# X99_20241008.net
KiCad netlist of a schematic drawn in Altium Designer
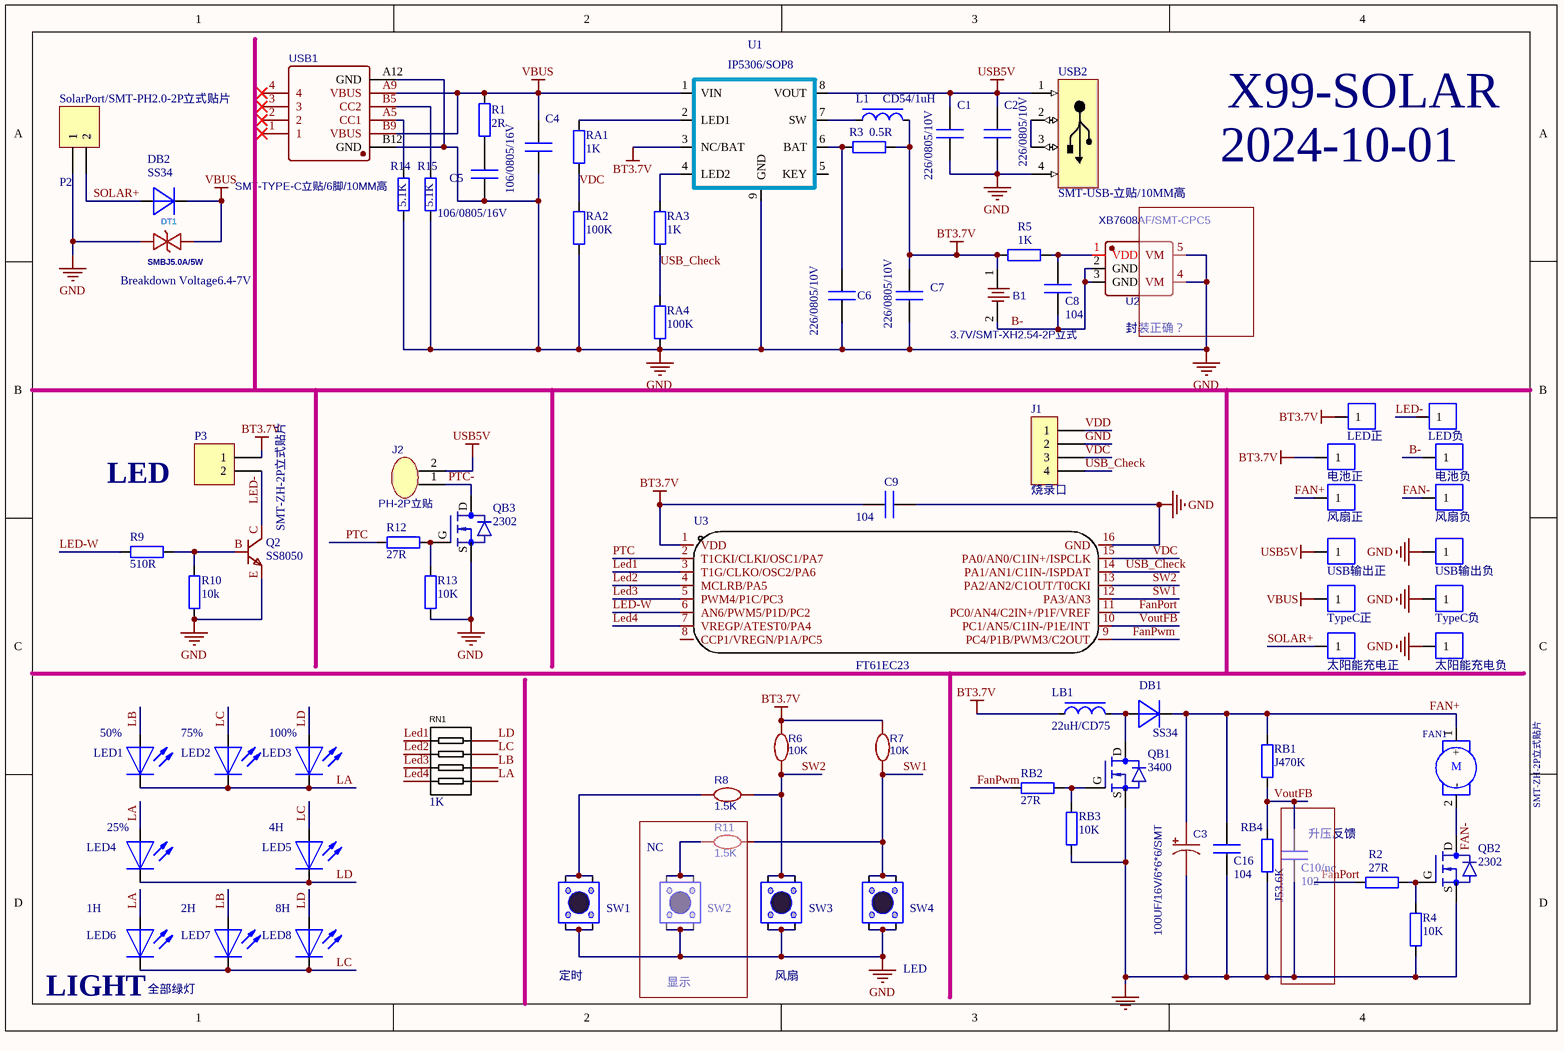
[diagram p0: X99_20241008.SchDoc]

(export (version "E")
  (design (tool "Eeschema 10.0.6"))
  (components
    (comp (ref "B1")
      (value "3.7V/SMT-XH2.54-2P立式")
      (footprint "SMT-XH2.54-2P立式")
      (fields (field (name "BOM_MANUFACTURER PART") "CR1220-2") (field (name "BOM_SUPPLIER PART") "C70381"))
      (libsource (lib "altium-import") (part "root_3_12V_"))
    )
    (comp (ref "C1")
      (value "226/0805/10V")
      (footprint "SMT-0805C")
      (libsource (lib "KENNED 原理图标准封装-20160624") (part "Cap"))
    )
    (comp (ref "C2")
      (value "226/0805/10V")
      (footprint "SMT-0805C")
      (libsource (lib "KENNED 原理图标准封装-20160624") (part "Cap"))
    )
    (comp (ref "C3")
      (value "100UF/16V/6*6*6/SMT")
      (footprint "CS 6*6 - V")
      (fields
        (field (name "BOM_SUPPLIER PART") "C365767")
        (field (name "BOM_MANUFACTURER PART") "RC050M4R7LO5*11TH-2A1E")
        (field (name "CONTRIBUTOR") "s-dawn")
      )
      (libsource (lib "altium-import") (part "root_0_220uF/35V_"))
    )
    (comp (ref "C4")
      (value "106/0805/16V")
      (footprint "SMT-0805C")
      (libsource (lib "KENNED 原理图标准封装-20160624") (part "Cap"))
    )
    (comp (ref "C5")
      (value "106/0805/16V")
      (footprint "SMT-0805C")
      (libsource (lib "KENNED 原理图标准封装-20160624") (part "Cap"))
    )
    (comp (ref "C6")
      (value "226/0805/10V")
      (footprint "SMT-0805C")
      (libsource (lib "KENNED 原理图标准封装-20160624") (part "Cap"))
    )
    (comp (ref "C7")
      (value "226/0805/10V")
      (footprint "SMT-0805C")
      (libsource (lib "KENNED 原理图标准封装-20160624") (part "Cap"))
    )
    (comp (ref "C8")
      (value "104")
      (footprint "SMT-0603C")
      (libsource (lib "KENNED 原理图标准封装-20160624") (part "Cap"))
    )
    (comp (ref "C9")
      (value "104")
      (footprint "SMT-0603C")
      (libsource (lib "KENNED 原理图标准封装-20180426") (part "Cap"))
    )
    (comp (ref "C10/nc")
      (value "102")
      (footprint "SMT-0603C")
      (libsource (lib "KENNED 原理图标准封装-20160624") (part "Cap"))
    )
    (comp (ref "C16")
      (value "104")
      (footprint "SMT-0603C")
      (libsource (lib "KENNED 原理图标准封装-20160624") (part "Cap"))
    )
    (comp (ref "DB1")
      (value "SS34")
      (footprint "SMT-SMA(DO-214AC)")
      (libsource (lib "KENNED 原理图标准封装-20180426") (part "Diode"))
    )
    (comp (ref "DB2")
      (value "SS34")
      (footprint "SMT-SMA(DO-214AC)")
      (libsource (lib "KENNED 原理图标准封装-20180426") (part "Diode"))
    )
    (comp (ref "DT1")
      (value "SMBJ5.0A/5W")
      (footprint "SMT-SMB(DO-214AA)")
      (fields (field (name "MANUFACTURER") "宏迦橙") (field (name "MANUFACTURER PART") "SMBJ5.0CA"))
      (libsource (lib "altium-import") (part "root_0_SMBJ5.0CA_C19077559_"))
    )
    (comp (ref "FAN1")
      (value "SMT-ZH-2P立式贴片")
      (footprint "SMT-ZH-2AB")
      (libsource (lib "*") (part "MotorDC-P"))
    )
    (comp (ref "J1") (value "烧录口") (footprint "SMT-烧录口") (libsource (lib "排针") (part "Pin HDR1X4")))
    (comp (ref "J2")
      (value "PH-2P立贴")
      (footprint "SMT-PH2.0-2P立式贴片")
      (fields (field (name "CONTRIBUTOR") "guilingSong"))
      (libsource (lib "altium-import") (part "root_0_mirrored_2P_"))
    )
    (comp (ref "L1")
      (value "CD54/1uH")
      (footprint "CD54")
      (libsource (lib "KENNED 原理图标准封装-20180426") (part "L Core"))
    )
    (comp (ref "LB1")
      (value "22uH/CD75")
      (footprint "SMT-CD75_L")
      (libsource (lib "KENNED 原理图标准封装-20180426") (part "L Core"))
    )
    (comp (ref "LED1")
      (value "~")
      (footprint "SMT-0603LED（绿灯）")
      (libsource (lib "KENNED 原理图标准封装-20160624") (part "LED"))
    )
    (comp (ref "LED2")
      (value "~")
      (footprint "SMT-0603LED（绿灯）")
      (libsource (lib "KENNED 原理图标准封装-20160624") (part "LED"))
    )
    (comp (ref "LED3")
      (value "~")
      (footprint "SMT-0603LED（绿灯）")
      (libsource (lib "KENNED 原理图标准封装-20160624") (part "LED"))
    )
    (comp (ref "LED4")
      (value "~")
      (footprint "SMT-0603LED（绿灯）")
      (libsource (lib "KENNED 原理图标准封装-20160624") (part "LED"))
    )
    (comp (ref "LED5")
      (value "~")
      (footprint "SMT-0603LED（绿灯）")
      (libsource (lib "KENNED 原理图标准封装-20160624") (part "LED"))
    )
    (comp (ref "LED6")
      (value "~")
      (footprint "SMT-0603LED（绿灯）")
      (libsource (lib "KENNED 原理图标准封装-20160624") (part "LED"))
    )
    (comp (ref "LED7")
      (value "~")
      (footprint "SMT-0603LED（绿灯）")
      (libsource (lib "KENNED 原理图标准封装-20160624") (part "LED"))
    )
    (comp (ref "LED8")
      (value "~")
      (footprint "SMT-0603LED（绿灯）")
      (libsource (lib "KENNED 原理图标准封装-20160624") (part "LED"))
    )
    (comp (ref "LED正")
      (value "测试点")
      (footprint "test3.0_top")
      (libsource (lib "KENNED 原理图标准封装-2023-9-7") (part "1P"))
    )
    (comp (ref "LED负")
      (value "测试点")
      (footprint "test3.0_top")
      (libsource (lib "KENNED 原理图标准封装-2023-9-7") (part "1P"))
    )
    (comp (ref "P2")
      (value "SolarPort/SMT-PH2.0-2P立式贴片")
      (footprint "SMT-PH2.0-2P立式贴片")
      (description "Header, 2-Pin")
      (fields (field (name "PUBLISHER") "Altium Limited"))
      (libsource (lib "") (part "Header 2_1"))
    )
    (comp (ref "P3")
      (value "SMT-ZH-2P立式贴片")
      (footprint "SMT-ZH-2AB")
      (description "Header, 2-Pin")
      (fields (field (name "PUBLISHER") "Altium Limited"))
      (libsource (lib "Safety-Others") (part "Header 2"))
    )
    (comp (ref "Q2")
      (value "SS8050")
      (footprint "SMT-SOT-23(BJT)")
      (libsource (lib "KENNED 原理图标准封装-2023-9-7") (part "NPN"))
    )
    (comp (ref "QB1")
      (value "3400")
      (footprint "SMT-SOT-23 (NMOS)")
      (libsource (lib "KENNED 原理图标准封装-2023-9-7") (part "N MOS"))
    )
    (comp (ref "QB2")
      (value "2302")
      (footprint "SMT-SOT-23 (NMOS)")
      (libsource (lib "KENNED 原理图标准封装-2023-9-7") (part "N MOS"))
    )
    (comp (ref "QB3")
      (value "2302")
      (footprint "SMT-SOT-23 (NMOS)")
      (libsource (lib "KENNED 原理图标准封装-2023-9-7") (part "N MOS"))
    )
    (comp (ref "R1")
      (value "2R")
      (footprint "SMT-0603R")
      (libsource (lib "KENNED 原理图标准封装-20160624") (part "Res"))
    )
    (comp (ref "R2") (value "27R") (footprint "SMT-0603R") (libsource (lib "*") (part "Res")))
    (comp (ref "R3")
      (value "0.5R")
      (footprint "SMT-0603R")
      (libsource (lib "KENNED 原理图标准封装-20160624") (part "Res"))
    )
    (comp (ref "R4") (value "10K") (footprint "SMT-0603R") (libsource (lib "*") (part "Res")))
    (comp (ref "R5")
      (value "1K")
      (footprint "SMT-0603R")
      (libsource (lib "KENNED 原理图标准封装-20160624") (part "Res"))
    )
    (comp (ref "R6")
      (value "10K")
      (footprint "SMT-0603R")
      (fields (field (name "CONTRIBUTOR") "LCEDA_Lib"))
      (libsource (lib "altium-import") (part "root_3_1k_"))
    )
    (comp (ref "R7")
      (value "10K")
      (footprint "SMT-0603R")
      (fields (field (name "CONTRIBUTOR") "LCEDA_Lib"))
      (libsource (lib "altium-import") (part "root_3_1k_"))
    )
    (comp (ref "R8")
      (value "1.5K")
      (footprint "SMT-0603R")
      (fields (field (name "CONTRIBUTOR") "LCEDA_Lib"))
      (libsource (lib "altium-import") (part "root_0_1k_"))
    )
    (comp (ref "R9") (value "510R") (footprint "SMT-0603R") (libsource (lib "*") (part "Res")))
    (comp (ref "R10") (value "10k") (footprint "SMT-0603R") (libsource (lib "*") (part "Res")))
    (comp (ref "R11")
      (value "1.5K")
      (footprint "SMT-0603R")
      (fields (field (name "CONTRIBUTOR") "LCEDA_Lib"))
      (libsource (lib "altium-import") (part "root_0_1k_"))
    )
    (comp (ref "R12") (value "27R") (footprint "SMT-0603R") (libsource (lib "*") (part "Res")))
    (comp (ref "R13") (value "10K") (footprint "SMT-0603R") (libsource (lib "*") (part "Res")))
    (comp (ref "R14")
      (value "5.1K")
      (footprint "0603_R")
      (libsource (lib "KENNED 原理图标准封装-20160624") (part "Res"))
    )
    (comp (ref "R15")
      (value "5.1K")
      (footprint "0603_R")
      (libsource (lib "KENNED 原理图标准封装-20160624") (part "Res"))
    )
    (comp (ref "RA1") (value "1K") (footprint "SMT-0603R") (libsource (lib "*") (part "Res")))
    (comp (ref "RA2") (value "100K") (footprint "SMT-0603R") (libsource (lib "*") (part "Res")))
    (comp (ref "RA3") (value "1K") (footprint "SMT-0603R") (libsource (lib "*") (part "Res")))
    (comp (ref "RA4") (value "100K") (footprint "SMT-0603R") (libsource (lib "*") (part "Res")))
    (comp (ref "RB1") (value "J470K") (footprint "SMT-0603R") (libsource (lib "*") (part "Res")))
    (comp (ref "RB2") (value "27R") (footprint "SMT-0603R") (libsource (lib "*") (part "Res")))
    (comp (ref "RB3") (value "10K") (footprint "SMT-0603R") (libsource (lib "*") (part "Res")))
    (comp (ref "RB4") (value "J53.6K") (footprint "SMT-0603R") (libsource (lib "*") (part "Res")))
    (comp (ref "RN1")
      (value "1K")
      (footprint "SMT0603*4")
      (fields (field (name "MANUFACTURER PART") "YC164-JR-070RL"))
      (libsource (lib "altium-import") (part "root_3_YC164-JR-070RL_"))
    )
    (comp (ref "SW1") (value "SMT-6X6*7.5") (footprint "SMT-6X6轻触开关通用") (libsource (lib "") (part "SW-4_2")))
    (comp (ref "SW2") (value "SMT-6X6*7.5") (footprint "SMT-6X6轻触开关通用") (libsource (lib "*") (part "SW-4")))
    (comp (ref "SW3") (value "SMT-6X6*7.5") (footprint "SMT-6X6轻触开关通用") (libsource (lib "") (part "SW-4_2")))
    (comp (ref "SW4") (value "SMT-6X6*7.5") (footprint "SMT-6X6轻触开关通用") (libsource (lib "") (part "SW-4_1")))
    (comp (ref "TypeC正")
      (value "测试点")
      (footprint "test3.0_top")
      (libsource (lib "KENNED 原理图标准封装-2023-9-7") (part "1P"))
    )
    (comp (ref "TypeC负")
      (value "测试点")
      (footprint "test3.0_top")
      (libsource (lib "KENNED 原理图标准封装-2023-9-7") (part "1P"))
    )
    (comp (ref "U1")
      (value "IP5306/SOP8")
      (footprint "SMT-ESOP-8 锡膏")
      (libsource (lib "黄植富") (part "IC-IP5303"))
    )
    (comp (ref "U2")
      (value "XB7608AF/SMT-CPC5")
      (footprint "SMT-CPC5")
      (fields
        (field (name "BOM_SUPPLIER PART") "C249345")
        (field (name "BOM_MANUFACTURER PART") "XB7608AF")
        (field (name "CONTRIBUTOR") "LCSC")
      )
      (libsource (lib "altium-import") (part "root_0_XB7608AF_"))
    )
    (comp (ref "U3")
      (value "FT61EC23")
      (footprint "SMT-SOP-16")
      (fields (field (name "MANUFACTURER PART") "FT61FC23-RB"))
      (libsource (lib "altium-import") (part "root_0_FT61FC23-RB_"))
    )
    (comp (ref "USB1")
      (value "SMT-TYPE-C立贴/6脚/10MM高")
      (footprint "SMT-TypeC-6P立式贴片(新)")
      (fields
        (field (name "BOM_SUPPLIER PART") "C283541")
        (field (name "BOM_MANUFACTURER PART") "TYPE-C-31-M-16")
        (field (name "CONTRIBUTOR") "LCSC")
      )
      (libsource (lib "altium-import") (part "root_2_TYPE-C-31-M-16_"))
    )
    (comp (ref "USB2") (value "SMT-USB-立贴/10MM高") (footprint "SMT-USB-立贴") (libsource (lib "*") (part "USB")))
    (comp (ref "USB输出正")
      (value "测试点")
      (footprint "test3.0_top")
      (libsource (lib "KENNED 原理图标准封装-2023-9-7") (part "1P"))
    )
    (comp (ref "USB输出负")
      (value "测试点")
      (footprint "test3.0_top")
      (libsource (lib "KENNED 原理图标准封装-2023-9-7") (part "1P"))
    )
    (comp (ref "太阳能充电正")
      (value "测试点")
      (footprint "test3.0_top")
      (libsource (lib "KENNED 原理图标准封装-2023-9-7") (part "1P"))
    )
    (comp (ref "太阳能充电负")
      (value "测试点")
      (footprint "test3.0_top")
      (libsource (lib "KENNED 原理图标准封装-2023-9-7") (part "1P"))
    )
    (comp (ref "电池正")
      (value "测试点")
      (footprint "test3.0_top")
      (libsource (lib "KENNED 原理图标准封装-2023-9-7") (part "1P"))
    )
    (comp (ref "电池负")
      (value "测试点")
      (footprint "test3.0_top")
      (libsource (lib "KENNED 原理图标准封装-2023-9-7") (part "1P"))
    )
    (comp (ref "风扇正")
      (value "测试点")
      (footprint "test3.0_top")
      (libsource (lib "KENNED 原理图标准封装-2023-9-7") (part "1P"))
    )
    (comp (ref "风扇负")
      (value "测试点")
      (footprint "test3.0_top")
      (libsource (lib "KENNED 原理图标准封装-2023-9-7") (part "1P"))
    )
  )
  (nets
    (net (code "1") (name "/B-") (class "Default")
      (node (ref "B1") (pin "2") (pinfunction "2_2") (pintype "passive"))
      (node (ref "C8") (pin "1") (pinfunction "1_1") (pintype "passive"))
      (node (ref "U2") (pin "2") (pinfunction "GND_2") (pintype "passive"))
      (node (ref "U2") (pin "3") (pinfunction "GND_3") (pintype "passive"))
      (node (ref "电池负") (pin "1") (pinfunction "1_1") (pintype "passive"))
    )
    (net (code "2") (name "/FAN+") (class "Default")
      (node (ref "C16") (pin "2") (pinfunction "2_2") (pintype "passive"))
      (node (ref "C3") (pin "1") (pinfunction "1_1") (pintype "passive"))
      (node (ref "DB1") (pin "2") (pinfunction "2_2") (pintype "passive"))
      (node (ref "FAN1") (pin "1") (pinfunction "+_1") (pintype "passive"))
      (node (ref "RB1") (pin "2") (pinfunction "2_2") (pintype "passive"))
      (node (ref "风扇正") (pin "1") (pinfunction "1_1") (pintype "passive"))
    )
    (net (code "3") (name "/FAN-") (class "Default")
      (node (ref "FAN1") (pin "2") (pinfunction "-_2") (pintype "passive"))
      (node (ref "QB2") (pin "D") (pinfunction "D_D") (pintype "passive"))
      (node (ref "风扇负") (pin "1") (pinfunction "1_1") (pintype "passive"))
    )
    (net (code "4") (name "/FanPort") (class "Default")
      (node (ref "R2") (pin "2") (pinfunction "2_2") (pintype "passive"))
      (node (ref "U3") (pin "11") (pinfunction "PC0/AN4/C2IN+/P1F/VREF_11") (pintype "passive"))
    )
    (net (code "5") (name "/FanPwm") (class "Default")
      (node (ref "RB2") (pin "1") (pinfunction "1_1") (pintype "passive"))
      (node (ref "U3") (pin "9") (pinfunction "PC4/P1B/PWM3/C2OUT_9") (pintype "passive"))
    )
    (net (code "6") (name "/LA") (class "Default")
      (node (ref "LED1") (pin "2") (pinfunction "2_2") (pintype "passive"))
      (node (ref "LED2") (pin "2") (pinfunction "2_2") (pintype "passive"))
      (node (ref "LED3") (pin "2") (pinfunction "2_2") (pintype "passive"))
      (node (ref "LED4") (pin "1") (pinfunction "1_1") (pintype "passive"))
      (node (ref "LED6") (pin "1") (pinfunction "1_1") (pintype "passive"))
      (node (ref "RN1") (pin "5") (pinfunction "5_5") (pintype "passive"))
    )
    (net (code "7") (name "/LB") (class "Default")
      (node (ref "LED1") (pin "1") (pinfunction "1_1") (pintype "passive"))
      (node (ref "LED7") (pin "1") (pinfunction "1_1") (pintype "passive"))
      (node (ref "RN1") (pin "6") (pinfunction "6_6") (pintype "passive"))
    )
    (net (code "8") (name "/LC") (class "Default")
      (node (ref "LED2") (pin "1") (pinfunction "1_1") (pintype "passive"))
      (node (ref "LED5") (pin "1") (pinfunction "1_1") (pintype "passive"))
      (node (ref "LED6") (pin "2") (pinfunction "2_2") (pintype "passive"))
      (node (ref "LED7") (pin "2") (pinfunction "2_2") (pintype "passive"))
      (node (ref "LED8") (pin "2") (pinfunction "2_2") (pintype "passive"))
      (node (ref "RN1") (pin "7") (pinfunction "7_7") (pintype "passive"))
    )
    (net (code "9") (name "/LD") (class "Default")
      (node (ref "LED3") (pin "1") (pinfunction "1_1") (pintype "passive"))
      (node (ref "LED4") (pin "2") (pinfunction "2_2") (pintype "passive"))
      (node (ref "LED5") (pin "2") (pinfunction "2_2") (pintype "passive"))
      (node (ref "LED8") (pin "1") (pinfunction "1_1") (pintype "passive"))
      (node (ref "RN1") (pin "8") (pinfunction "8_8") (pintype "passive"))
    )
    (net (code "10") (name "/LED-") (class "Default")
      (node (ref "LED负") (pin "1") (pinfunction "1_1") (pintype "passive"))
      (node (ref "P3") (pin "2") (pinfunction "2_2") (pintype "passive"))
      (node (ref "Q2") (pin "C") (pinfunction "C_C") (pintype "passive"))
    )
    (net (code "11") (name "/LED-W") (class "Default")
      (node (ref "R9") (pin "1") (pinfunction "1_1") (pintype "passive"))
      (node (ref "U3") (pin "6") (pinfunction "AN6/PWM5/P1D/PC2_6") (pintype "passive"))
    )
    (net (code "12") (name "/Led1") (class "Default")
      (node (ref "RN1") (pin "1") (pinfunction "1_1") (pintype "passive"))
      (node (ref "U3") (pin "3") (pinfunction "T1G/CLKO/OSC2/PA6_3") (pintype "passive"))
    )
    (net (code "13") (name "/Led2") (class "Default")
      (node (ref "RN1") (pin "2") (pinfunction "2_2") (pintype "passive"))
      (node (ref "U3") (pin "4") (pinfunction "MCLRB/PA5_4") (pintype "passive"))
    )
    (net (code "14") (name "/Led3") (class "Default")
      (node (ref "RN1") (pin "3") (pinfunction "3_3") (pintype "passive"))
      (node (ref "U3") (pin "5") (pinfunction "PWM4/P1C/PC3_5") (pintype "passive"))
    )
    (net (code "15") (name "/Led4") (class "Default")
      (node (ref "RN1") (pin "4") (pinfunction "4_4") (pintype "passive"))
      (node (ref "U3") (pin "7") (pinfunction "VREGP/ATEST0/PA4_7") (pintype "passive"))
    )
    (net (code "16") (name "/PTC") (class "Default")
      (node (ref "R12") (pin "2") (pinfunction "2_2") (pintype "passive"))
      (node (ref "U3") (pin "2") (pinfunction "T1CKI/CLKI/OSC1/PA7_2") (pintype "passive"))
    )
    (net (code "17") (name "/PTC-") (class "Default")
      (node (ref "J2") (pin "1") (pintype "passive"))
      (node (ref "QB3") (pin "D") (pinfunction "D_D") (pintype "passive"))
    )
    (net (code "18") (name "/SOLAR+") (class "Default")
      (node (ref "DB2") (pin "1") (pinfunction "1_1") (pintype "passive"))
      (node (ref "P2") (pin "2") (pinfunction "2_2") (pintype "passive"))
      (node (ref "太阳能充电正") (pin "1") (pinfunction "1_1") (pintype "passive"))
    )
    (net (code "19") (name "/SW1") (class "Default")
      (node (ref "R11") (pin "2") (pinfunction "2_2") (pintype "passive"))
      (node (ref "R7") (pin "2") (pinfunction "2_2") (pintype "passive"))
      (node (ref "SW4") (pin "2") (pintype "passive"))
      (node (ref "SW4") (pin "4") (pintype "passive"))
      (node (ref "U3") (pin "12") (pinfunction "PA3/AN3_12") (pintype "passive"))
    )
    (net (code "20") (name "/SW2") (class "Default")
      (node (ref "R6") (pin "2") (pinfunction "2_2") (pintype "passive"))
      (node (ref "R8") (pin "2") (pinfunction "2_2") (pintype "passive"))
      (node (ref "SW3") (pin "2") (pintype "passive"))
      (node (ref "SW3") (pin "4") (pintype "passive"))
      (node (ref "U3") (pin "13") (pinfunction "PA2/AN2/C1OUT/T0CKI_13") (pintype "passive"))
    )
    (net (code "21") (name "/USB_Check") (class "Default")
      (node (ref "J1") (pin "4") (pinfunction "4_4") (pintype "passive"))
      (node (ref "RA3") (pin "1") (pinfunction "1_1") (pintype "passive"))
      (node (ref "RA4") (pin "2") (pinfunction "2_2") (pintype "passive"))
      (node (ref "U3") (pin "14") (pinfunction "PA1/AN1/C1IN-/ISPDAT_14") (pintype "passive"))
    )
    (net (code "22") (name "/VDC") (class "Default")
      (node (ref "J1") (pin "3") (pinfunction "3_3") (pintype "passive"))
      (node (ref "RA1") (pin "1") (pinfunction "1_1") (pintype "passive"))
      (node (ref "RA2") (pin "2") (pinfunction "2_2") (pintype "passive"))
      (node (ref "U3") (pin "15") (pinfunction "PA0/AN0/C1IN+/ISPCLK_15") (pintype "passive"))
    )
    (net (code "23") (name "/VDD") (class "Default")
      (node (ref "J1") (pin "1") (pinfunction "1_1") (pintype "passive"))
    )
    (net (code "24") (name "/VoutFB") (class "Default")
      (node (ref "C10/nc") (pin "2") (pinfunction "2_2") (pintype "passive"))
      (node (ref "RB1") (pin "1") (pinfunction "1_1") (pintype "passive"))
      (node (ref "RB4") (pin "2") (pinfunction "2_2") (pintype "passive"))
      (node (ref "U3") (pin "10") (pinfunction "PC1/AN5/C1IN-/P1E/INT_10") (pintype "passive"))
    )
    (net (code "25") (name "BT3.7V") (class "Default")
      (node (ref "B1") (pin "1") (pinfunction "1_1") (pintype "passive"))
      (node (ref "C7") (pin "2") (pinfunction "2_2") (pintype "passive"))
      (node (ref "C9") (pin "2") (pinfunction "2_2") (pintype "passive"))
      (node (ref "L1") (pin "2") (pinfunction "2_2") (pintype "passive"))
      (node (ref "LB1") (pin "1") (pinfunction "1_1") (pintype "passive"))
      (node (ref "LED正") (pin "1") (pinfunction "1_1") (pintype "passive"))
      (node (ref "P3") (pin "1") (pinfunction "1_1") (pintype "passive"))
      (node (ref "R3") (pin "1") (pinfunction "1_1") (pintype "passive"))
      (node (ref "R5") (pin "2") (pinfunction "2_2") (pintype "passive"))
      (node (ref "R6") (pin "1") (pinfunction "1_1") (pintype "passive"))
      (node (ref "R7") (pin "1") (pinfunction "1_1") (pintype "passive"))
      (node (ref "U1") (pin "3") (pinfunction "NC/BAT_3") (pintype "passive"))
      (node (ref "U3") (pin "1") (pinfunction "VDD_1") (pintype "passive"))
      (node (ref "电池正") (pin "1") (pinfunction "1_1") (pintype "passive"))
    )
    (net (code "26") (name "GND") (class "Default")
      (node (ref "C1") (pin "1") (pinfunction "1_1") (pintype "passive"))
      (node (ref "C10/nc") (pin "1") (pinfunction "1_1") (pintype "passive"))
      (node (ref "C16") (pin "1") (pinfunction "1_1") (pintype "passive"))
      (node (ref "C2") (pin "1") (pinfunction "1_1") (pintype "passive"))
      (node (ref "C3") (pin "2") (pinfunction "2_2") (pintype "passive"))
      (node (ref "C4") (pin "1") (pinfunction "1_1") (pintype "passive"))
      (node (ref "C5") (pin "1") (pinfunction "1_1") (pintype "passive"))
      (node (ref "C6") (pin "2") (pinfunction "2_2") (pintype "passive"))
      (node (ref "C7") (pin "1") (pinfunction "1_1") (pintype "passive"))
      (node (ref "C9") (pin "1") (pinfunction "1_1") (pintype "passive"))
      (node (ref "DT1") (pin "1") (pinfunction "1_1") (pintype "passive"))
      (node (ref "J1") (pin "2") (pinfunction "2_2") (pintype "passive"))
      (node (ref "P2") (pin "1") (pinfunction "1_1") (pintype "passive"))
      (node (ref "Q2") (pin "E") (pinfunction "E_E") (pintype "passive"))
      (node (ref "QB1") (pin "S") (pinfunction "S_S") (pintype "passive"))
      (node (ref "QB2") (pin "S") (pinfunction "S_S") (pintype "passive"))
      (node (ref "QB3") (pin "S") (pinfunction "S_S") (pintype "passive"))
      (node (ref "R10") (pin "1") (pinfunction "1_1") (pintype "passive"))
      (node (ref "R13") (pin "1") (pinfunction "1_1") (pintype "passive"))
      (node (ref "R14") (pin "2") (pinfunction "2_2") (pintype "passive"))
      (node (ref "R15") (pin "2") (pinfunction "2_2") (pintype "passive"))
      (node (ref "R4") (pin "1") (pinfunction "1_1") (pintype "passive"))
      (node (ref "RA2") (pin "1") (pinfunction "1_1") (pintype "passive"))
      (node (ref "RA4") (pin "1") (pinfunction "1_1") (pintype "passive"))
      (node (ref "RB3") (pin "1") (pinfunction "1_1") (pintype "passive"))
      (node (ref "RB4") (pin "1") (pinfunction "1_1") (pintype "passive"))
      (node (ref "SW1") (pin "1") (pintype "passive"))
      (node (ref "SW1") (pin "3") (pintype "passive"))
      (node (ref "SW2") (pin "1") (pintype "passive"))
      (node (ref "SW2") (pin "3") (pintype "passive"))
      (node (ref "SW3") (pin "1") (pintype "passive"))
      (node (ref "SW3") (pin "3") (pintype "passive"))
      (node (ref "SW4") (pin "1") (pintype "passive"))
      (node (ref "SW4") (pin "3") (pintype "passive"))
      (node (ref "TypeC负") (pin "1") (pinfunction "1_1") (pintype "passive"))
      (node (ref "U1") (pin "9") (pinfunction "GND_9") (pintype "passive"))
      (node (ref "U2") (pin "4") (pinfunction "VM_4") (pintype "passive"))
      (node (ref "U2") (pin "5") (pinfunction "VM_5") (pintype "passive"))
      (node (ref "U3") (pin "16") (pinfunction "GND_16") (pintype "passive"))
      (node (ref "USB1") (pin "A12") (pinfunction "GND_A12") (pintype "passive"))
      (node (ref "USB1") (pin "B12") (pinfunction "GND_B12") (pintype "passive"))
      (node (ref "USB2") (pin "4") (pinfunction "4_4") (pintype "input"))
      (node (ref "USB输出负") (pin "1") (pinfunction "1_1") (pintype "passive"))
      (node (ref "太阳能充电负") (pin "1") (pinfunction "1_1") (pintype "passive"))
    )
    (net (code "27") (name "Net-(C5-Pad2)") (class "Default")
      (node (ref "C5") (pin "2") (pinfunction "2_2") (pintype "passive"))
      (node (ref "R1") (pin "1") (pinfunction "1_1") (pintype "passive"))
    )
    (net (code "28") (name "Net-(DB1-Pad1)") (class "Default")
      (node (ref "DB1") (pin "1") (pinfunction "1_1") (pintype "passive"))
      (node (ref "LB1") (pin "2") (pinfunction "2_2") (pintype "passive"))
      (node (ref "QB1") (pin "D") (pinfunction "D_D") (pintype "passive"))
    )
    (net (code "29") (name "Net-(Q2-PadB)") (class "Default")
      (node (ref "Q2") (pin "B") (pinfunction "B_B") (pintype "passive"))
      (node (ref "R10") (pin "2") (pinfunction "2_2") (pintype "passive"))
      (node (ref "R9") (pin "2") (pinfunction "2_2") (pintype "passive"))
    )
    (net (code "30") (name "Net-(QB1-PadG)") (class "Default")
      (node (ref "QB1") (pin "G") (pinfunction "G_G") (pintype "passive"))
      (node (ref "RB2") (pin "2") (pinfunction "2_2") (pintype "passive"))
      (node (ref "RB3") (pin "2") (pinfunction "2_2") (pintype "passive"))
    )
    (net (code "31") (name "Net-(QB2-PadG)") (class "Default")
      (node (ref "QB2") (pin "G") (pinfunction "G_G") (pintype "passive"))
      (node (ref "R2") (pin "1") (pinfunction "1_1") (pintype "passive"))
      (node (ref "R4") (pin "2") (pinfunction "2_2") (pintype "passive"))
    )
    (net (code "32") (name "Net-(QB3-PadG)") (class "Default")
      (node (ref "QB3") (pin "G") (pinfunction "G_G") (pintype "passive"))
      (node (ref "R12") (pin "1") (pinfunction "1_1") (pintype "passive"))
      (node (ref "R13") (pin "2") (pinfunction "2_2") (pintype "passive"))
    )
    (net (code "33") (name "Net-(R8-Pad1)") (class "Default")
      (node (ref "R8") (pin "1") (pinfunction "1_1") (pintype "passive"))
      (node (ref "SW1") (pin "2") (pintype "passive"))
      (node (ref "SW1") (pin "4") (pintype "passive"))
    )
    (net (code "34") (name "Net-(R11-Pad1)") (class "Default")
      (node (ref "R11") (pin "1") (pinfunction "1_1") (pintype "passive"))
      (node (ref "SW2") (pin "2") (pintype "passive"))
      (node (ref "SW2") (pin "4") (pintype "passive"))
    )
    (net (code "35") (name "Net-(U1-BAT)") (class "Default")
      (node (ref "C6") (pin "1") (pinfunction "1_1") (pintype "passive"))
      (node (ref "R3") (pin "2") (pinfunction "2_2") (pintype "passive"))
      (node (ref "U1") (pin "6") (pinfunction "BAT_6") (pintype "passive"))
    )
    (net (code "36") (name "Net-(U1-LED1)") (class "Default")
      (node (ref "RA1") (pin "2") (pinfunction "2_2") (pintype "passive"))
      (node (ref "U1") (pin "2") (pinfunction "LED1_2") (pintype "passive"))
    )
    (net (code "37") (name "Net-(U1-LED2)") (class "Default")
      (node (ref "RA3") (pin "2") (pinfunction "2_2") (pintype "passive"))
      (node (ref "U1") (pin "4") (pinfunction "LED2_4") (pintype "passive"))
    )
    (net (code "38") (name "Net-(U1-SW)") (class "Default")
      (node (ref "L1") (pin "1") (pinfunction "1_1") (pintype "passive"))
      (node (ref "U1") (pin "7") (pinfunction "SW_7") (pintype "passive"))
    )
    (net (code "39") (name "Net-(U2-VDD)") (class "Default")
      (node (ref "C8") (pin "2") (pinfunction "2_2") (pintype "passive"))
      (node (ref "R5") (pin "1") (pinfunction "1_1") (pintype "passive"))
      (node (ref "U2") (pin "1") (pinfunction "VDD_1") (pintype "passive"))
    )
    (net (code "40") (name "Net-(USB1-CC1)") (class "Default")
      (node (ref "R14") (pin "1") (pinfunction "1_1") (pintype "passive"))
      (node (ref "USB1") (pin "A5") (pinfunction "CC1_A5") (pintype "passive"))
    )
    (net (code "41") (name "Net-(USB1-CC2)") (class "Default")
      (node (ref "R15") (pin "1") (pinfunction "1_1") (pintype "passive"))
      (node (ref "USB1") (pin "B5") (pinfunction "CC2_B5") (pintype "passive"))
    )
    (net (code "42") (name "Net-(USB2-Pad2)") (class "Default")
      (node (ref "USB2") (pin "2") (pinfunction "2_2") (pintype "bidirectional"))
      (node (ref "USB2") (pin "3") (pinfunction "3_3") (pintype "bidirectional"))
    )
    (net (code "43") (name "USB5V") (class "Default")
      (node (ref "C1") (pin "2") (pinfunction "2_2") (pintype "passive"))
      (node (ref "C2") (pin "2") (pinfunction "2_2") (pintype "passive"))
      (node (ref "J2") (pin "2") (pintype "passive"))
      (node (ref "U1") (pin "8") (pinfunction "VOUT_8") (pintype "passive"))
      (node (ref "USB2") (pin "1") (pinfunction "1_1") (pintype "input"))
      (node (ref "USB输出正") (pin "1") (pinfunction "1_1") (pintype "passive"))
    )
    (net (code "44") (name "VBUS") (class "Default")
      (node (ref "C4") (pin "2") (pinfunction "2_2") (pintype "passive"))
      (node (ref "DB2") (pin "2") (pinfunction "2_2") (pintype "passive"))
      (node (ref "DT1") (pin "2") (pinfunction "2_2") (pintype "passive"))
      (node (ref "R1") (pin "2") (pinfunction "2_2") (pintype "passive"))
      (node (ref "TypeC正") (pin "1") (pinfunction "1_1") (pintype "passive"))
      (node (ref "U1") (pin "1") (pinfunction "VIN_1") (pintype "passive"))
      (node (ref "USB1") (pin "A9") (pinfunction "VBUS_A9") (pintype "passive"))
      (node (ref "USB1") (pin "B9") (pinfunction "VBUS_B9") (pintype "passive"))
    )
    (net (code "45") (name "unconnected-(U1-KEY-Pad5)") (class "Default")
      (node (ref "U1") (pin "5") (pinfunction "KEY_5") (pintype "passive"))
    )
    (net (code "46") (name "unconnected-(U3-CCP1{slash}VREGN{slash}P1A{slash}PC5-Pad8)") (class "Default")
      (node (ref "U3") (pin "8") (pinfunction "CCP1/VREGN/P1A/PC5_8") (pintype "passive"))
    )
    (net (code "47") (name "unconnected-(USB1-Pad1)") (class "Default")
      (node (ref "USB1") (pin "1") (pinfunction "1_1") (pintype "passive+no_connect"))
    )
    (net (code "48") (name "unconnected-(USB1-Pad2)") (class "Default")
      (node (ref "USB1") (pin "2") (pinfunction "2_2") (pintype "passive+no_connect"))
    )
    (net (code "49") (name "unconnected-(USB1-Pad3)") (class "Default")
      (node (ref "USB1") (pin "3") (pinfunction "3_3") (pintype "passive+no_connect"))
    )
    (net (code "50") (name "unconnected-(USB1-Pad4)") (class "Default")
      (node (ref "USB1") (pin "4") (pinfunction "4_4") (pintype "passive+no_connect"))
    )
  )
)
